# YiWallet-Enc-memory.net
KiCad netlist of a schematic drawn in Altium Designer
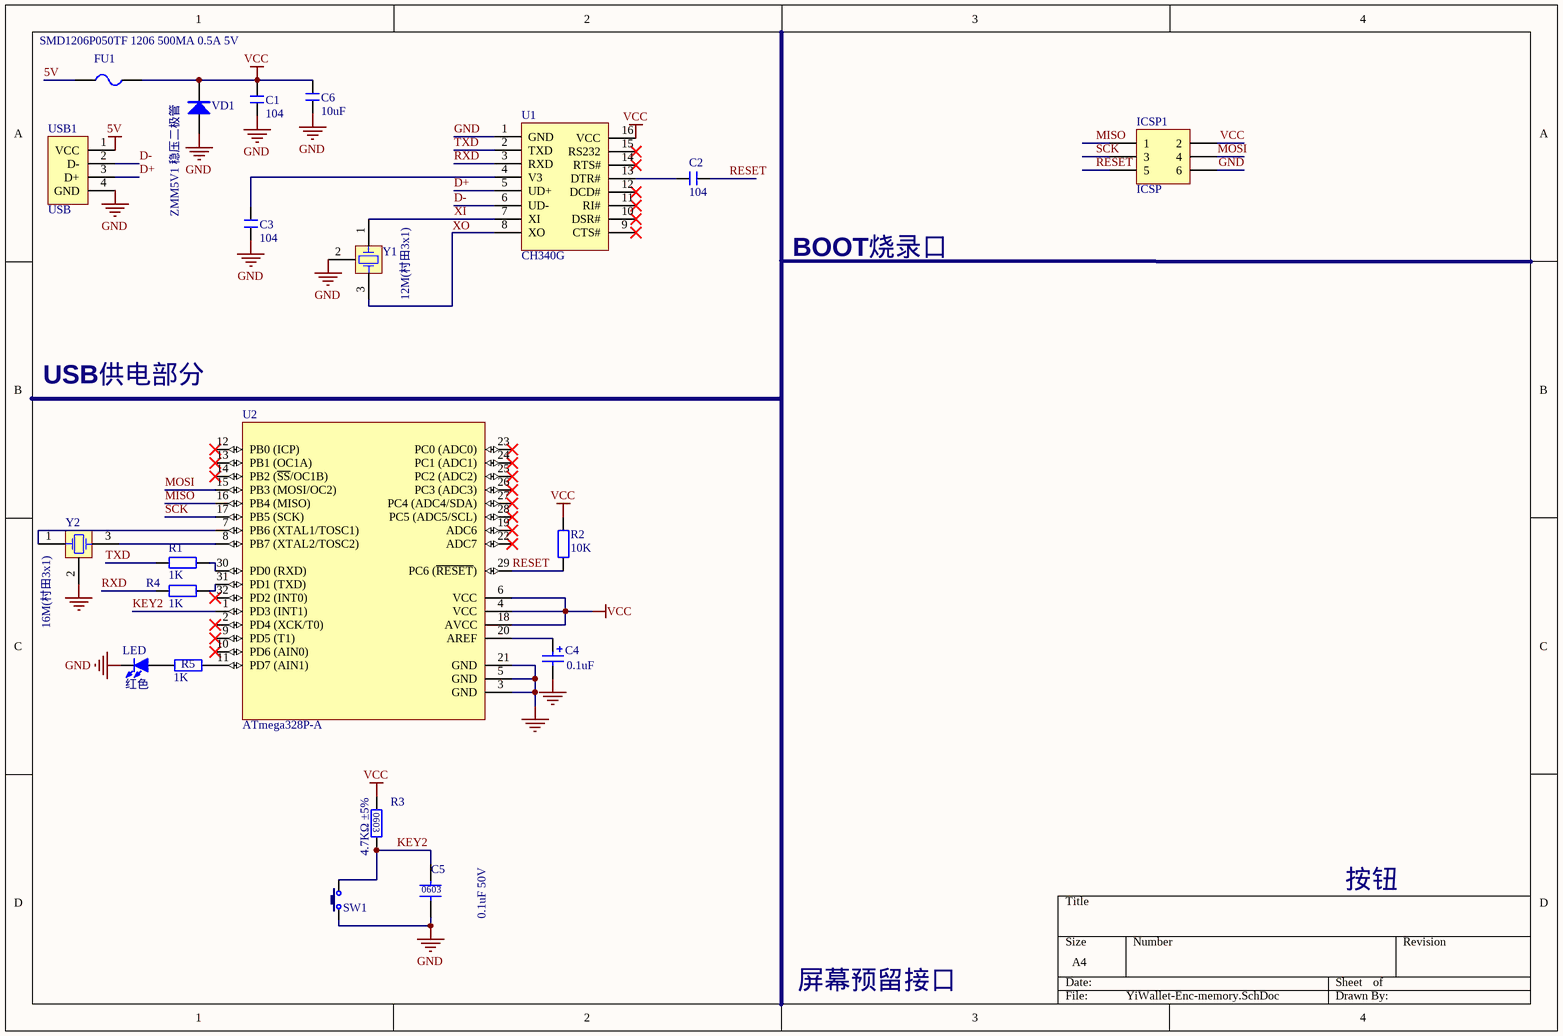
[diagram p0: YiWallet-Enc-memory.SchDoc]

(export (version "E")
  (design (tool "Eeschema 10.0.6"))
  (components
    (comp (ref "C1")
      (value "104")
      (footprint "C 0603_L")
      (description "无极性贴片电容")
      (fields (field (name "版权归属") "源创客"))
      (libsource (lib "3.1   - 电阻-电容-电感") (part "C"))
    )
    (comp (ref "C2")
      (value "104")
      (footprint "C 0603_L")
      (description "无极性贴片电容")
      (fields (field (name "版权归属") "源创客"))
      (libsource (lib "3.1   - 电阻-电容-电感") (part "C"))
    )
    (comp (ref "C3")
      (value "104")
      (footprint "C 0603_L")
      (description "无极性贴片电容")
      (fields (field (name "版权归属") "源创客"))
      (libsource (lib "3.1   - 电阻-电容-电感") (part "C"))
    )
    (comp (ref "C4")
      (value "0.1uF")
      (footprint "C 0603_L")
      (description "Polarized Capacitor (Surface Mount)")
      (fields (field (name "PUBLISHER") "Altium Limited"))
      (libsource (lib "Miscellaneous Devices") (part "Cap Pol3"))
    )
    (comp (ref "C5")
      (value "0.1uF 50V")
      (footprint "C 0603_L")
      (description "贴片电容 0.1uF 50V ±10% -55~+125℃ 0603 X7R CL10B104KB8NNNC")
      (libsource (lib "CLOU-BZ-BetaV0") (part "C-0.1uF 50V 0603"))
    )
    (comp (ref "C6")
      (value "10uF")
      (footprint "C 0603_L")
      (description "无极性贴片电容")
      (fields (field (name "版权归属") "源创客"))
      (libsource (lib "3.1   - 电阻-电容-电感") (part "C"))
    )
    (comp (ref "FU1")
      (value "SMD1206P050TF 1206 500MA 0.5A 5V")
      (footprint "FU 1206")
      (description "贴片保险丝")
      (fields (field (name "版权归属") "源创客"))
      (libsource (lib "10.1 - 保险丝-晶振") (part "FU"))
    )
    (comp (ref "ICSP1")
      (value "ICSP")
      (footprint "PH2.0-LI-6P")
      (description "Header, 3-Pin, Dual row")
      (fields (field (name "PUBLISHER") "Altium Limited"))
      (libsource (lib "Miscellaneous Connectors") (part "Header 3X2"))
    )
    (comp (ref "LED")
      (value "红色")
      (footprint "LED 0603G")
      (description "贴片LED")
      (fields (field (name "版权归属") "源创客"))
      (libsource (lib "9.1   - LED") (part "LED-SMD"))
    )
    (comp (ref "R1")
      (value "1K")
      (footprint "R 0603_L")
      (description "贴片电阻")
      (fields (field (name "版权归属") "源创客"))
      (libsource (lib "3.1   - 电阻-电容-电感") (part "R"))
    )
    (comp (ref "R2")
      (value "10K")
      (footprint "R 0603_L")
      (description "贴片电阻")
      (fields (field (name "版权归属") "源创客"))
      (libsource (lib "3.1   - 电阻-电容-电感") (part "R"))
    )
    (comp (ref "R3")
      (value "4.7KΩ ±5%")
      (footprint "C 0603_L")
      (description "贴片电阻 4.7KΩ 1/10W ±5% ±200ppm 0603")
      (libsource (lib "CLOU-BZ-BetaV0") (part "R-4K7 0603 5%"))
    )
    (comp (ref "R4")
      (value "1K")
      (footprint "R 0603_L")
      (description "贴片电阻")
      (fields (field (name "版权归属") "源创客"))
      (libsource (lib "3.1   - 电阻-电容-电感") (part "R"))
    )
    (comp (ref "R5")
      (value "1K")
      (footprint "R 0603_L")
      (description "贴片电阻")
      (fields (field (name "版权归属") "源创客"))
      (libsource (lib "3.1   - 电阻-电容-电感") (part "R"))
    )
    (comp (ref "SW1")
      (value "3x6x5")
      (footprint "TSW SMD-3*6*2.5")
      (description "3x6轻触开关")
      (fields (field (name "版权归属") "源创客"))
      (libsource (lib "5.1   - 按键-开关") (part "TSW 3x6"))
    )
    (comp (ref "U1") (value "CH340G") (footprint "SO-16") (libsource (lib "PCB_Project") (part "CH340G")))
    (comp (ref "U2")
      (value "ATmega328P-A")
      (footprint "TQFP32-7*7")
      (description "8-Bit AVR Microcontroller with 8K Bytes of In-System Programmable Flash Memory")
      (libsource (lib "Atmel Microcontroller 8-Bit AVR") (part "ATmega8-16AC"))
    )
    (comp (ref "USB1")
      (value "USB")
      (footprint "USB_A/P_A")
      (description "USB-A型公接口")
      (fields (field (name "版权归属") "源创客"))
      (libsource (lib "4.1   - 接口类") (part "USB-A/P"))
    )
    (comp (ref "VD1")
      (value "ZMM5V1 稳压二极管")
      (footprint "MINI_MELF (LL34)")
      (description "高速开关二极管")
      (fields (field (name "版权归属") "源创客"))
      (libsource (lib "8.1   - 二极管-整流桥") (part "1N4148"))
    )
    (comp (ref "Y1")
      (value "12M(村田3x1)")
      (footprint "X-CPX20")
      (description "Crystal Oscillator, 3rd In-Line Lead Version")
      (fields (field (name "PUBLISHER") "Altium Limited"))
      (libsource (lib "") (part "ECS-35-17-4-3IL_1"))
    )
    (comp (ref "Y2")
      (value "16M(村田3x1)")
      (footprint "X-CPX20")
      (description "Crystal Oscillator, 3rd In-Line Lead Version")
      (fields (field (name "PUBLISHER") "Altium Limited"))
      (libsource (lib "ECS Crystal Oscillator") (part "ECS-35-17-4-3IL"))
    )
  )
  (nets
    (net (code "1") (name "/D+") (class "Default")
      (node (ref "U1") (pin "5") (pinfunction "UD+_5") (pintype "passive"))
      (node (ref "USB1") (pin "3") (pinfunction "D+_3") (pintype "passive"))
    )
    (net (code "2") (name "/D-") (class "Default")
      (node (ref "U1") (pin "6") (pinfunction "UD-_6") (pintype "passive"))
      (node (ref "USB1") (pin "2") (pinfunction "D-_2") (pintype "passive"))
    )
    (net (code "3") (name "/KEY2") (class "Default")
      (node (ref "C5") (pin "1") (pinfunction "1_1") (pintype "passive"))
      (node (ref "R3") (pin "2") (pinfunction "2_2") (pintype "passive"))
      (node (ref "SW1") (pin "2") (pinfunction "2_2") (pintype "passive"))
      (node (ref "U2") (pin "1") (pinfunction "PD3_(INT1)_1") (pintype "bidirectional"))
    )
    (net (code "4") (name "/MISO") (class "Default")
      (node (ref "ICSP1") (pin "1") (pinfunction "1_1") (pintype "passive"))
      (node (ref "U2") (pin "16") (pinfunction "PB4_(MISO)_16") (pintype "bidirectional"))
    )
    (net (code "5") (name "/MOSI") (class "Default")
      (node (ref "ICSP1") (pin "4") (pinfunction "4_4") (pintype "passive"))
      (node (ref "U2") (pin "15") (pinfunction "PB3_(MOSI/OC2)_15") (pintype "bidirectional"))
    )
    (net (code "6") (name "/RESET") (class "Default")
      (node (ref "C2") (pin "2") (pinfunction "2_2") (pintype "passive"))
      (node (ref "ICSP1") (pin "5") (pinfunction "5_5") (pintype "passive"))
      (node (ref "R2") (pin "1") (pinfunction "1_1") (pintype "passive"))
      (node (ref "U2") (pin "29") (pinfunction "PC6_(~{RESET})_29") (pintype "bidirectional"))
    )
    (net (code "7") (name "/RXD") (class "Default")
      (node (ref "R4") (pin "2") (pinfunction "2_2") (pintype "passive"))
      (node (ref "U1") (pin "3") (pinfunction "RXD_3") (pintype "passive"))
    )
    (net (code "8") (name "/SCK") (class "Default")
      (node (ref "ICSP1") (pin "3") (pinfunction "3_3") (pintype "passive"))
      (node (ref "U2") (pin "17") (pinfunction "PB5_(SCK)_17") (pintype "bidirectional"))
    )
    (net (code "9") (name "/TXD") (class "Default")
      (node (ref "R1") (pin "2") (pinfunction "2_2") (pintype "passive"))
      (node (ref "U1") (pin "2") (pinfunction "TXD_2") (pintype "passive"))
    )
    (net (code "10") (name "/XI") (class "Default")
      (node (ref "U1") (pin "7") (pinfunction "XI_7") (pintype "passive"))
      (node (ref "Y1") (pin "1") (pinfunction "OSC1_1") (pintype "passive"))
    )
    (net (code "11") (name "/XO") (class "Default")
      (node (ref "U1") (pin "8") (pinfunction "XO_8") (pintype "passive"))
      (node (ref "Y1") (pin "3") (pinfunction "OSC2_3") (pintype "passive"))
    )
    (net (code "12") (name "5V") (class "Default")
      (node (ref "FU1") (pin "1") (pinfunction "1_1") (pintype "passive"))
      (node (ref "USB1") (pin "1") (pinfunction "VCC_1") (pintype "passive"))
    )
    (net (code "13") (name "GND") (class "Default")
      (node (ref "C1") (pin "1") (pinfunction "1_1") (pintype "passive"))
      (node (ref "C3") (pin "1") (pinfunction "1_1") (pintype "passive"))
      (node (ref "C4") (pin "2") (pinfunction "2_2") (pintype "passive"))
      (node (ref "C5") (pin "2") (pinfunction "2_2") (pintype "passive"))
      (node (ref "C6") (pin "1") (pinfunction "1_1") (pintype "passive"))
      (node (ref "ICSP1") (pin "6") (pinfunction "6_6") (pintype "passive"))
      (node (ref "LED") (pin "2") (pinfunction "K_2") (pintype "passive"))
      (node (ref "SW1") (pin "1") (pinfunction "1_1") (pintype "passive"))
      (node (ref "U1") (pin "1") (pinfunction "GND_1") (pintype "passive"))
      (node (ref "U2") (pin "21") (pinfunction "GND_21") (pintype "power_in"))
      (node (ref "U2") (pin "3") (pinfunction "GND_3") (pintype "power_in"))
      (node (ref "U2") (pin "5") (pinfunction "GND_5") (pintype "power_in"))
      (node (ref "USB1") (pin "4") (pinfunction "GND_4") (pintype "passive"))
      (node (ref "VD1") (pin "1") (pinfunction "A_1") (pintype "passive"))
      (node (ref "Y1") (pin "2") (pinfunction "COM_2") (pintype "passive"))
      (node (ref "Y2") (pin "2") (pinfunction "COM_2") (pintype "passive"))
    )
    (net (code "14") (name "Net-(LED-A)") (class "Default")
      (node (ref "LED") (pin "1") (pinfunction "A_1") (pintype "passive"))
      (node (ref "R5") (pin "2") (pinfunction "2_2") (pintype "passive"))
    )
    (net (code "15") (name "Net-(U1-DTR#)") (class "Default")
      (node (ref "C2") (pin "1") (pinfunction "1_1") (pintype "passive"))
      (node (ref "U1") (pin "13") (pinfunction "DTR#_13") (pintype "passive"))
    )
    (net (code "16") (name "Net-(U1-V3)") (class "Default")
      (node (ref "C3") (pin "2") (pinfunction "2_2") (pintype "passive"))
      (node (ref "U1") (pin "4") (pinfunction "V3_4") (pintype "passive"))
    )
    (net (code "17") (name "Net-(U2-AREF)") (class "Default")
      (node (ref "C4") (pin "1") (pinfunction "1_1") (pintype "passive"))
      (node (ref "U2") (pin "20") (pinfunction "AREF_20") (pintype "passive"))
    )
    (net (code "18") (name "Net-(U2-PB6_(XTAL1{slash}TOSC1))") (class "Default")
      (node (ref "U2") (pin "7") (pinfunction "PB6_(XTAL1/TOSC1)_7") (pintype "bidirectional"))
      (node (ref "Y2") (pin "1") (pinfunction "OSC1_1") (pintype "passive"))
    )
    (net (code "19") (name "Net-(U2-PB7_(XTAL2{slash}TOSC2))") (class "Default")
      (node (ref "U2") (pin "8") (pinfunction "PB7_(XTAL2/TOSC2)_8") (pintype "bidirectional"))
      (node (ref "Y2") (pin "3") (pinfunction "OSC2_3") (pintype "passive"))
    )
    (net (code "20") (name "Net-(U2-PD0_(RXD))") (class "Default")
      (node (ref "R1") (pin "1") (pinfunction "1_1") (pintype "passive"))
      (node (ref "U2") (pin "30") (pinfunction "PD0_(RXD)_30") (pintype "bidirectional"))
    )
    (net (code "21") (name "Net-(U2-PD1_(TXD))") (class "Default")
      (node (ref "R4") (pin "1") (pinfunction "1_1") (pintype "passive"))
      (node (ref "U2") (pin "31") (pinfunction "PD1_(TXD)_31") (pintype "bidirectional"))
    )
    (net (code "22") (name "Net-(U2-PD7_(AIN1))") (class "Default")
      (node (ref "R5") (pin "1") (pinfunction "1_1") (pintype "passive"))
      (node (ref "U2") (pin "11") (pinfunction "PD7_(AIN1)_11") (pintype "bidirectional"))
    )
    (net (code "23") (name "VCC") (class "Default")
      (node (ref "C1") (pin "2") (pinfunction "2_2") (pintype "passive"))
      (node (ref "C6") (pin "2") (pinfunction "2_2") (pintype "passive"))
      (node (ref "FU1") (pin "2") (pinfunction "2_2") (pintype "passive"))
      (node (ref "ICSP1") (pin "2") (pinfunction "2_2") (pintype "passive"))
      (node (ref "R2") (pin "2") (pinfunction "2_2") (pintype "passive"))
      (node (ref "R3") (pin "1") (pinfunction "1_1") (pintype "passive"))
      (node (ref "U1") (pin "16") (pinfunction "VCC_16") (pintype "passive"))
      (node (ref "U2") (pin "18") (pinfunction "AVCC_18") (pintype "power_in"))
      (node (ref "U2") (pin "4") (pinfunction "VCC_4") (pintype "power_in"))
      (node (ref "U2") (pin "6") (pinfunction "VCC_6") (pintype "power_in"))
      (node (ref "VD1") (pin "2") (pinfunction "K_2") (pintype "passive"))
    )
    (net (code "24") (name "unconnected-(U1-CTS#-Pad9)") (class "Default")
      (node (ref "U1") (pin "9") (pinfunction "CTS#_9") (pintype "passive+no_connect"))
    )
    (net (code "25") (name "unconnected-(U1-DCD#-Pad12)") (class "Default")
      (node (ref "U1") (pin "12") (pinfunction "DCD#_12") (pintype "passive+no_connect"))
    )
    (net (code "26") (name "unconnected-(U1-DSR#-Pad10)") (class "Default")
      (node (ref "U1") (pin "10") (pinfunction "DSR#_10") (pintype "passive+no_connect"))
    )
    (net (code "27") (name "unconnected-(U1-RI#-Pad11)") (class "Default")
      (node (ref "U1") (pin "11") (pinfunction "RI#_11") (pintype "passive+no_connect"))
    )
    (net (code "28") (name "unconnected-(U1-RS232-Pad15)") (class "Default")
      (node (ref "U1") (pin "15") (pinfunction "RS232_15") (pintype "passive+no_connect"))
    )
    (net (code "29") (name "unconnected-(U1-RTS#-Pad14)") (class "Default")
      (node (ref "U1") (pin "14") (pinfunction "RTS#_14") (pintype "passive+no_connect"))
    )
    (net (code "30") (name "unconnected-(U2-ADC6-Pad19)") (class "Default")
      (node (ref "U2") (pin "19") (pinfunction "ADC6_19") (pintype "bidirectional+no_connect"))
    )
    (net (code "31") (name "unconnected-(U2-ADC7-Pad22)") (class "Default")
      (node (ref "U2") (pin "22") (pinfunction "ADC7_22") (pintype "bidirectional+no_connect"))
    )
    (net (code "32") (name "unconnected-(U2-PB0_(ICP)-Pad12)") (class "Default")
      (node (ref "U2") (pin "12") (pinfunction "PB0_(ICP)_12") (pintype "bidirectional+no_connect"))
    )
    (net (code "33") (name "unconnected-(U2-PB1_(OC1A)-Pad13)") (class "Default")
      (node (ref "U2") (pin "13") (pinfunction "PB1_(OC1A)_13") (pintype "bidirectional+no_connect"))
    )
    (net (code "34") (name "unconnected-(U2-PB2_(~{SS}{slash}OC1B)-Pad14)") (class "Default")
      (node (ref "U2") (pin "14") (pinfunction "PB2_(~{SS}/OC1B)_14") (pintype "bidirectional+no_connect"))
    )
    (net (code "35") (name "unconnected-(U2-PC0_(ADC0)-Pad23)") (class "Default")
      (node (ref "U2") (pin "23") (pinfunction "PC0_(ADC0)_23") (pintype "bidirectional+no_connect"))
    )
    (net (code "36") (name "unconnected-(U2-PC1_(ADC1)-Pad24)") (class "Default")
      (node (ref "U2") (pin "24") (pinfunction "PC1_(ADC1)_24") (pintype "bidirectional+no_connect"))
    )
    (net (code "37") (name "unconnected-(U2-PC2_(ADC2)-Pad25)") (class "Default")
      (node (ref "U2") (pin "25") (pinfunction "PC2_(ADC2)_25") (pintype "bidirectional+no_connect"))
    )
    (net (code "38") (name "unconnected-(U2-PC3_(ADC3)-Pad26)") (class "Default")
      (node (ref "U2") (pin "26") (pinfunction "PC3_(ADC3)_26") (pintype "bidirectional+no_connect"))
    )
    (net (code "39") (name "unconnected-(U2-PC4_(ADC4{slash}SDA)-Pad27)") (class "Default")
      (node (ref "U2") (pin "27") (pinfunction "PC4_(ADC4/SDA)_27") (pintype "bidirectional+no_connect"))
    )
    (net (code "40") (name "unconnected-(U2-PC5_(ADC5{slash}SCL)-Pad28)") (class "Default")
      (node (ref "U2") (pin "28") (pinfunction "PC5_(ADC5/SCL)_28") (pintype "bidirectional+no_connect"))
    )
    (net (code "41") (name "unconnected-(U2-PD2_(INT0)-Pad32)") (class "Default")
      (node (ref "U2") (pin "32") (pinfunction "PD2_(INT0)_32") (pintype "bidirectional+no_connect"))
    )
    (net (code "42") (name "unconnected-(U2-PD4_(XCK{slash}T0)-Pad2)") (class "Default")
      (node (ref "U2") (pin "2") (pinfunction "PD4_(XCK/T0)_2") (pintype "bidirectional+no_connect"))
    )
    (net (code "43") (name "unconnected-(U2-PD5_(T1)-Pad9)") (class "Default")
      (node (ref "U2") (pin "9") (pinfunction "PD5_(T1)_9") (pintype "bidirectional+no_connect"))
    )
    (net (code "44") (name "unconnected-(U2-PD6_(AIN0)-Pad10)") (class "Default")
      (node (ref "U2") (pin "10") (pinfunction "PD6_(AIN0)_10") (pintype "bidirectional+no_connect"))
    )
  )
)
